# untitled.net
KiCad netlist of a schematic drawn in EAGLE
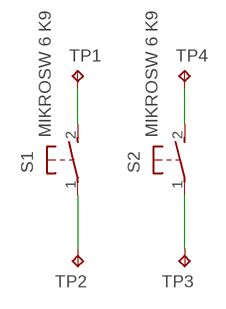
[diagram p0: schematic, sheet 1]

(export (version "E")
  (design (tool "Eeschema 10.0.6"))
  (components
    (comp (ref "S1")
      (value "MIKROSW 6 K9")
      (footprint "eagle-import:MIKROSW_6_K9")
      (libsource (lib "eagle-import") (part "KAN0631-090-X-X"))
    )
    (comp (ref "S2")
      (value "MIKROSW 6 K9")
      (footprint "eagle-import:MIKROSW_6_K9")
      (libsource (lib "eagle-import") (part "KAN0631-090-X-X"))
    )
    (comp (ref "TP1")
      (value "TPPAD1-13Y")
      (footprint "eagle-import:P1-13Y")
      (libsource (lib "eagle-import") (part "TPPAD1-13Y"))
    )
    (comp (ref "TP2")
      (value "TPPAD1-13Y")
      (footprint "eagle-import:P1-13Y")
      (libsource (lib "eagle-import") (part "TPPAD1-13Y"))
    )
    (comp (ref "TP3")
      (value "TPPAD1-13Y")
      (footprint "eagle-import:P1-13Y")
      (libsource (lib "eagle-import") (part "TPPAD1-13Y"))
    )
    (comp (ref "TP4")
      (value "TPPAD1-13Y")
      (footprint "eagle-import:P1-13Y")
      (libsource (lib "eagle-import") (part "TPPAD1-13Y"))
    )
  )
  (nets
    (net (code "1") (name "Net-(S1-P)") (class "Default")
      (node (ref "S1") (pin "1") (pinfunction "P_1") (pintype "passive"))
      (node (ref "TP2") (pin "TP") (pinfunction "TP_TP") (pintype "input"))
    )
    (net (code "2") (name "Net-(S1-S)") (class "Default")
      (node (ref "S1") (pin "2") (pinfunction "S_2") (pintype "passive"))
      (node (ref "TP1") (pin "TP") (pinfunction "TP_TP") (pintype "input"))
    )
    (net (code "3") (name "Net-(S2-P)") (class "Default")
      (node (ref "S2") (pin "1") (pinfunction "P_1") (pintype "passive"))
      (node (ref "TP3") (pin "TP") (pinfunction "TP_TP") (pintype "input"))
    )
    (net (code "4") (name "Net-(S2-S)") (class "Default")
      (node (ref "S2") (pin "2") (pinfunction "S_2") (pintype "passive"))
      (node (ref "TP4") (pin "TP") (pinfunction "TP_TP") (pintype "input"))
    )
  )
)
